# Button.net
KiCad netlist of a schematic drawn in Altium Designer
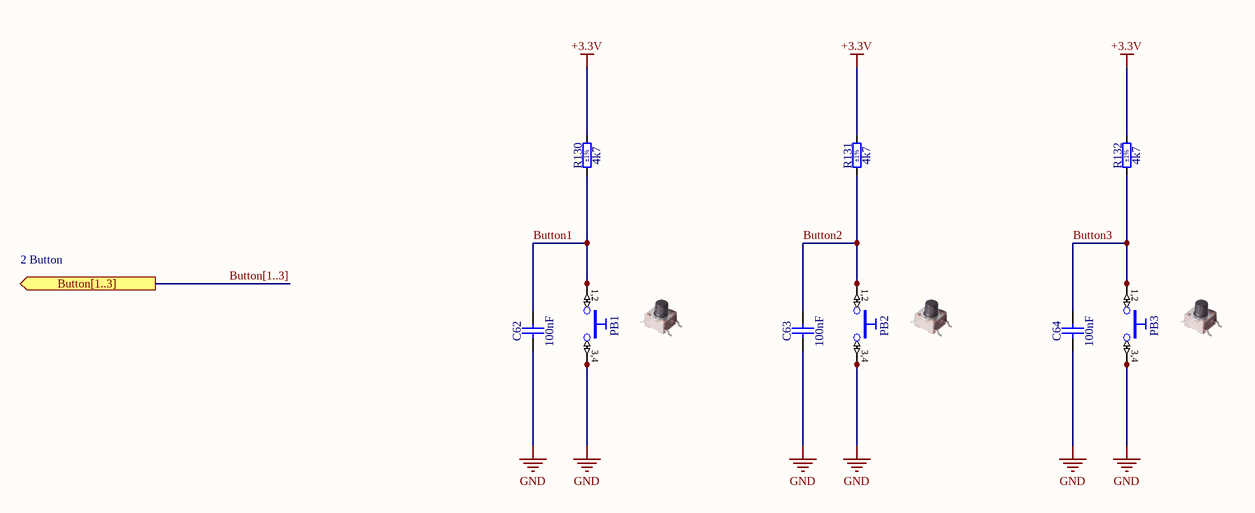
[diagram p0: Button.SchDoc]

(export (version "E")
  (design (tool "Eeschema 10.0.6"))
  (components
    (comp (ref "C62")
      (value "100nF")
      (footprint "CAPC1608X87N")
      (description "Non-polarised capacitor")
      (fields
        (field (name "PART NUMBER") "CC0603_100NF_50V_10%_X7R")
        (field (name "VOLTAGE") "50V")
        (field (name "AUTHOR") "CERN DEM JLC")
      )
      (libsource (lib "Capacitors") (part "Capacitor - non polarized"))
    )
    (comp (ref "C63")
      (value "100nF")
      (footprint "CAPC1608X87N")
      (description "Non-polarised capacitor")
      (fields
        (field (name "PART NUMBER") "CC0603_100NF_50V_10%_X7R")
        (field (name "VOLTAGE") "50V")
        (field (name "AUTHOR") "CERN DEM JLC")
      )
      (libsource (lib "Capacitors") (part "Capacitor - non polarized"))
    )
    (comp (ref "C64")
      (value "100nF")
      (footprint "CAPC1608X87N")
      (description "Non-polarised capacitor")
      (fields
        (field (name "PART NUMBER") "CC0603_100NF_50V_10%_X7R")
        (field (name "VOLTAGE") "50V")
        (field (name "AUTHOR") "CERN DEM JLC")
      )
      (libsource (lib "Capacitors") (part "Capacitor - non polarized"))
    )
    (comp (ref "PB1")
      (value "Push Button")
      (footprint "PB_TYCO_FSM6JSMA")
      (description "Push-Button Switch SPDT")
      (fields
        (field (name "PART NUMBER") "PB_TYCO_FSM6JSMA")
        (field (name "MANUFACTURER") "TYCO ELECTRONICS")
        (field (name "AUTHOR") "CERN DEM JLC")
      )
      (libsource (lib "Eletro-mechanical") (part "PB SPST 12NO-34NO"))
    )
    (comp (ref "PB2")
      (value "Push Button")
      (footprint "PB_TYCO_FSM6JSMA")
      (description "Push-Button Switch SPDT")
      (fields
        (field (name "PART NUMBER") "PB_TYCO_FSM6JSMA")
        (field (name "MANUFACTURER") "TYCO ELECTRONICS")
        (field (name "AUTHOR") "CERN DEM JLC")
      )
      (libsource (lib "Eletro-mechanical") (part "PB SPST 12NO-34NO"))
    )
    (comp (ref "PB3")
      (value "Push Button")
      (footprint "PB_TYCO_FSM6JSMA")
      (description "Push-Button Switch SPDT")
      (fields
        (field (name "PART NUMBER") "PB_TYCO_FSM6JSMA")
        (field (name "MANUFACTURER") "TYCO ELECTRONICS")
        (field (name "AUTHOR") "CERN DEM JLC")
      )
      (libsource (lib "Eletro-mechanical") (part "PB SPST 12NO-34NO"))
    )
    (comp (ref "R130")
      (value "4k7")
      (footprint "RESC1608X55N")
      (description "Resistor - 1%")
      (fields
        (field (name "TOLERANCE") "±1%")
        (field (name "PART NUMBER") "R0603_4K7_1%_0.1W_100PPM")
        (field (name "POWER") "0.1W")
        (field (name "AUTHOR") "CERN DEM JLC")
      )
      (libsource (lib "Resistors") (part "Resistor - 1%"))
    )
    (comp (ref "R131")
      (value "4k7")
      (footprint "RESC1608X55N")
      (description "Resistor - 1%")
      (fields
        (field (name "TOLERANCE") "±1%")
        (field (name "PART NUMBER") "R0603_4K7_1%_0.1W_100PPM")
        (field (name "POWER") "0.1W")
        (field (name "AUTHOR") "CERN DEM JLC")
      )
      (libsource (lib "Resistors") (part "Resistor - 1%"))
    )
    (comp (ref "R132")
      (value "4k7")
      (footprint "RESC1608X55N")
      (description "Resistor - 1%")
      (fields
        (field (name "TOLERANCE") "±1%")
        (field (name "PART NUMBER") "R0603_4K7_1%_0.1W_100PPM")
        (field (name "POWER") "0.1W")
        (field (name "AUTHOR") "CERN DEM JLC")
      )
      (libsource (lib "Resistors") (part "Resistor - 1%"))
    )
  )
  (nets
    (net (code "1") (name "+3.3V") (class "Default")
      (node (ref "R130") (pin "2") (pinfunction "2_2") (pintype "passive"))
      (node (ref "R131") (pin "2") (pinfunction "2_2") (pintype "passive"))
      (node (ref "R132") (pin "2") (pinfunction "2_2") (pintype "passive"))
    )
    (net (code "2") (name "/Button1") (class "Default")
      (node (ref "C62") (pin "2") (pinfunction "2_2") (pintype "passive"))
      (node (ref "PB1") (pin "1") (pinfunction "1_1") (pintype "bidirectional"))
      (node (ref "PB1") (pin "2") (pinfunction "2_2") (pintype "bidirectional"))
      (node (ref "R130") (pin "1") (pinfunction "1_1") (pintype "passive"))
    )
    (net (code "3") (name "/Button2") (class "Default")
      (node (ref "C63") (pin "2") (pinfunction "2_2") (pintype "passive"))
      (node (ref "PB2") (pin "1") (pinfunction "1_1") (pintype "bidirectional"))
      (node (ref "PB2") (pin "2") (pinfunction "2_2") (pintype "bidirectional"))
      (node (ref "R131") (pin "1") (pinfunction "1_1") (pintype "passive"))
    )
    (net (code "4") (name "/Button3") (class "Default")
      (node (ref "C64") (pin "2") (pinfunction "2_2") (pintype "passive"))
      (node (ref "PB3") (pin "1") (pinfunction "1_1") (pintype "bidirectional"))
      (node (ref "PB3") (pin "2") (pinfunction "2_2") (pintype "bidirectional"))
      (node (ref "R132") (pin "1") (pinfunction "1_1") (pintype "passive"))
    )
    (net (code "6") (name "GND") (class "Default")
      (node (ref "C62") (pin "1") (pinfunction "1_1") (pintype "passive"))
      (node (ref "C63") (pin "1") (pinfunction "1_1") (pintype "passive"))
      (node (ref "C64") (pin "1") (pinfunction "1_1") (pintype "passive"))
      (node (ref "PB1") (pin "3") (pinfunction "3_3") (pintype "bidirectional"))
      (node (ref "PB1") (pin "4") (pinfunction "4_4") (pintype "bidirectional"))
      (node (ref "PB2") (pin "3") (pinfunction "3_3") (pintype "bidirectional"))
      (node (ref "PB2") (pin "4") (pinfunction "4_4") (pintype "bidirectional"))
      (node (ref "PB3") (pin "3") (pinfunction "3_3") (pintype "bidirectional"))
      (node (ref "PB3") (pin "4") (pinfunction "4_4") (pintype "bidirectional"))
    )
  )
)
